# BoardTsu.net
KiCad netlist of a schematic drawn in EAGLE
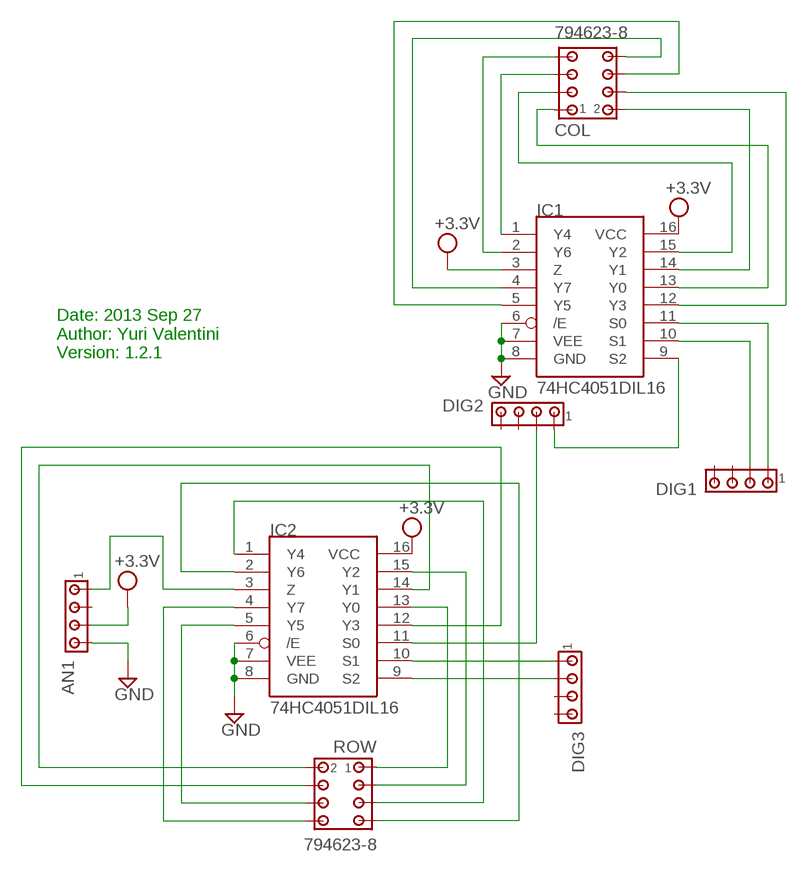
[diagram p0: schematic, sheet 1]

(export (version "E")
  (design (tool "Eeschema 10.0.6"))
  (components
    (comp (ref "AN1")
      (value "MTA04-156")
      (footprint "eagle-import:1X4MTA")
      (libsource (lib "eagle-import") (part "MTA04-156"))
    )
    (comp (ref "COL")
      (value "794623-8")
      (footprint "eagle-import:794623-8")
      (libsource (lib "eagle-import") (part "794623-8"))
    )
    (comp (ref "DIG1")
      (value "MTA04-156")
      (footprint "eagle-import:1X4MTA")
      (libsource (lib "eagle-import") (part "MTA04-156"))
    )
    (comp (ref "DIG2")
      (value "MTA04-156")
      (footprint "eagle-import:1X4MTA")
      (libsource (lib "eagle-import") (part "MTA04-156"))
    )
    (comp (ref "DIG3")
      (value "MTA04-156")
      (footprint "eagle-import:1X4MTA")
      (libsource (lib "eagle-import") (part "MTA04-156"))
    )
    (comp (ref "IC1")
      (value "74HC4051DIL16")
      (footprint "eagle-import:DIL16")
      (libsource (lib "eagle-import") (part "74HC4051DIL16"))
    )
    (comp (ref "IC2")
      (value "74HC4051DIL16")
      (footprint "eagle-import:DIL16")
      (libsource (lib "eagle-import") (part "74HC4051DIL16"))
    )
    (comp (ref "ROW")
      (value "794623-8")
      (footprint "eagle-import:794623-8")
      (libsource (lib "eagle-import") (part "794623-8"))
    )
  )
  (nets
    (net (code "1") (name "+3.3V") (class "Default")
      (node (ref "AN1") (pin "3") (pinfunction "3_3") (pintype "passive"))
      (node (ref "IC1") (pin "16") (pinfunction "VCC_16") (pintype "bidirectional"))
      (node (ref "IC1") (pin "3") (pinfunction "Z_3") (pintype "bidirectional"))
      (node (ref "IC2") (pin "16") (pinfunction "VCC_16") (pintype "bidirectional"))
    )
    (net (code "2") (name "GND") (class "Default")
      (node (ref "AN1") (pin "4") (pinfunction "4_4") (pintype "passive"))
      (node (ref "IC1") (pin "6") (pinfunction "/E_6") (pintype "bidirectional"))
      (node (ref "IC1") (pin "7") (pinfunction "VEE_7") (pintype "bidirectional"))
      (node (ref "IC1") (pin "8") (pinfunction "GND_8") (pintype "bidirectional"))
      (node (ref "IC2") (pin "6") (pinfunction "/E_6") (pintype "bidirectional"))
      (node (ref "IC2") (pin "7") (pinfunction "VEE_7") (pintype "bidirectional"))
      (node (ref "IC2") (pin "8") (pinfunction "GND_8") (pintype "bidirectional"))
    )
    (net (code "3") (name "Net-(IC1-S0)") (class "Default")
      (node (ref "DIG1") (pin "1") (pinfunction "1_1") (pintype "passive"))
      (node (ref "IC1") (pin "11") (pinfunction "S0_11") (pintype "bidirectional"))
    )
    (net (code "4") (name "Net-(IC1-S1)") (class "Default")
      (node (ref "DIG1") (pin "2") (pinfunction "2_2") (pintype "passive"))
      (node (ref "IC1") (pin "10") (pinfunction "S1_10") (pintype "bidirectional"))
    )
    (net (code "5") (name "Net-(IC1-S2)") (class "Default")
      (node (ref "DIG2") (pin "1") (pinfunction "1_1") (pintype "passive"))
      (node (ref "IC1") (pin "9") (pinfunction "S2_9") (pintype "bidirectional"))
    )
    (net (code "6") (name "Net-(IC1-Y0)") (class "Default")
      (node (ref "COL") (pin "1") (pinfunction "1_1") (pintype "passive"))
      (node (ref "IC1") (pin "13") (pinfunction "Y0_13") (pintype "bidirectional"))
    )
    (net (code "7") (name "Net-(IC1-Y1)") (class "Default")
      (node (ref "COL") (pin "2") (pinfunction "2_2") (pintype "passive"))
      (node (ref "IC1") (pin "14") (pinfunction "Y1_14") (pintype "bidirectional"))
    )
    (net (code "8") (name "Net-(IC1-Y2)") (class "Default")
      (node (ref "COL") (pin "3") (pinfunction "3_3") (pintype "passive"))
      (node (ref "IC1") (pin "15") (pinfunction "Y2_15") (pintype "bidirectional"))
    )
    (net (code "9") (name "Net-(IC1-Y3)") (class "Default")
      (node (ref "COL") (pin "4") (pinfunction "4_4") (pintype "passive"))
      (node (ref "IC1") (pin "12") (pinfunction "Y3_12") (pintype "bidirectional"))
    )
    (net (code "10") (name "Net-(IC1-Y4)") (class "Default")
      (node (ref "COL") (pin "5") (pinfunction "5_5") (pintype "passive"))
      (node (ref "IC1") (pin "1") (pinfunction "Y4_1") (pintype "bidirectional"))
    )
    (net (code "11") (name "Net-(IC1-Y5)") (class "Default")
      (node (ref "COL") (pin "6") (pinfunction "6_6") (pintype "passive"))
      (node (ref "IC1") (pin "5") (pinfunction "Y5_5") (pintype "bidirectional"))
    )
    (net (code "12") (name "Net-(IC1-Y6)") (class "Default")
      (node (ref "COL") (pin "7") (pinfunction "7_7") (pintype "passive"))
      (node (ref "IC1") (pin "2") (pinfunction "Y6_2") (pintype "bidirectional"))
    )
    (net (code "13") (name "Net-(IC1-Y7)") (class "Default")
      (node (ref "COL") (pin "8") (pinfunction "8_8") (pintype "passive"))
      (node (ref "IC1") (pin "4") (pinfunction "Y7_4") (pintype "bidirectional"))
    )
    (net (code "14") (name "Net-(IC2-S0)") (class "Default")
      (node (ref "DIG2") (pin "2") (pinfunction "2_2") (pintype "passive"))
      (node (ref "IC2") (pin "11") (pinfunction "S0_11") (pintype "bidirectional"))
    )
    (net (code "15") (name "Net-(IC2-S1)") (class "Default")
      (node (ref "DIG3") (pin "1") (pinfunction "1_1") (pintype "passive"))
      (node (ref "IC2") (pin "10") (pinfunction "S1_10") (pintype "bidirectional"))
    )
    (net (code "16") (name "Net-(IC2-S2)") (class "Default")
      (node (ref "DIG3") (pin "2") (pinfunction "2_2") (pintype "passive"))
      (node (ref "IC2") (pin "9") (pinfunction "S2_9") (pintype "bidirectional"))
    )
    (net (code "17") (name "Net-(IC2-Y0)") (class "Default")
      (node (ref "IC2") (pin "13") (pinfunction "Y0_13") (pintype "bidirectional"))
      (node (ref "ROW") (pin "1") (pinfunction "1_1") (pintype "passive"))
    )
    (net (code "18") (name "Net-(IC2-Y1)") (class "Default")
      (node (ref "IC2") (pin "14") (pinfunction "Y1_14") (pintype "bidirectional"))
      (node (ref "ROW") (pin "2") (pinfunction "2_2") (pintype "passive"))
    )
    (net (code "19") (name "Net-(IC2-Y2)") (class "Default")
      (node (ref "IC2") (pin "15") (pinfunction "Y2_15") (pintype "bidirectional"))
      (node (ref "ROW") (pin "3") (pinfunction "3_3") (pintype "passive"))
    )
    (net (code "20") (name "Net-(IC2-Y3)") (class "Default")
      (node (ref "IC2") (pin "12") (pinfunction "Y3_12") (pintype "bidirectional"))
      (node (ref "ROW") (pin "4") (pinfunction "4_4") (pintype "passive"))
    )
    (net (code "21") (name "Net-(IC2-Y4)") (class "Default")
      (node (ref "IC2") (pin "1") (pinfunction "Y4_1") (pintype "bidirectional"))
      (node (ref "ROW") (pin "5") (pinfunction "5_5") (pintype "passive"))
    )
    (net (code "22") (name "Net-(IC2-Y5)") (class "Default")
      (node (ref "IC2") (pin "5") (pinfunction "Y5_5") (pintype "bidirectional"))
      (node (ref "ROW") (pin "6") (pinfunction "6_6") (pintype "passive"))
    )
    (net (code "23") (name "Net-(IC2-Y6)") (class "Default")
      (node (ref "IC2") (pin "2") (pinfunction "Y6_2") (pintype "bidirectional"))
      (node (ref "ROW") (pin "7") (pinfunction "7_7") (pintype "passive"))
    )
    (net (code "24") (name "Net-(IC2-Y7)") (class "Default")
      (node (ref "IC2") (pin "4") (pinfunction "Y7_4") (pintype "bidirectional"))
      (node (ref "ROW") (pin "8") (pinfunction "8_8") (pintype "passive"))
    )
    (net (code "25") (name "Net-(IC2-Z)") (class "Default")
      (node (ref "AN1") (pin "1") (pinfunction "1_1") (pintype "passive"))
      (node (ref "IC2") (pin "3") (pinfunction "Z_3") (pintype "bidirectional"))
    )
    (net (code "26") (name "unconnected-(AN1-Pad2)") (class "Default")
      (node (ref "AN1") (pin "2") (pinfunction "2_2") (pintype "passive"))
    )
    (net (code "27") (name "unconnected-(DIG1-Pad3)") (class "Default")
      (node (ref "DIG1") (pin "3") (pinfunction "3_3") (pintype "passive"))
    )
    (net (code "28") (name "unconnected-(DIG1-Pad4)") (class "Default")
      (node (ref "DIG1") (pin "4") (pinfunction "4_4") (pintype "passive"))
    )
    (net (code "29") (name "unconnected-(DIG2-Pad3)") (class "Default")
      (node (ref "DIG2") (pin "3") (pinfunction "3_3") (pintype "passive"))
    )
    (net (code "30") (name "unconnected-(DIG2-Pad4)") (class "Default")
      (node (ref "DIG2") (pin "4") (pinfunction "4_4") (pintype "passive"))
    )
    (net (code "31") (name "unconnected-(DIG3-Pad3)") (class "Default")
      (node (ref "DIG3") (pin "3") (pinfunction "3_3") (pintype "passive"))
    )
    (net (code "32") (name "unconnected-(DIG3-Pad4)") (class "Default")
      (node (ref "DIG3") (pin "4") (pinfunction "4_4") (pintype "passive"))
    )
  )
)
